# Knobber_Topsheet.net
KiCad netlist of a schematic drawn in Altium Designer
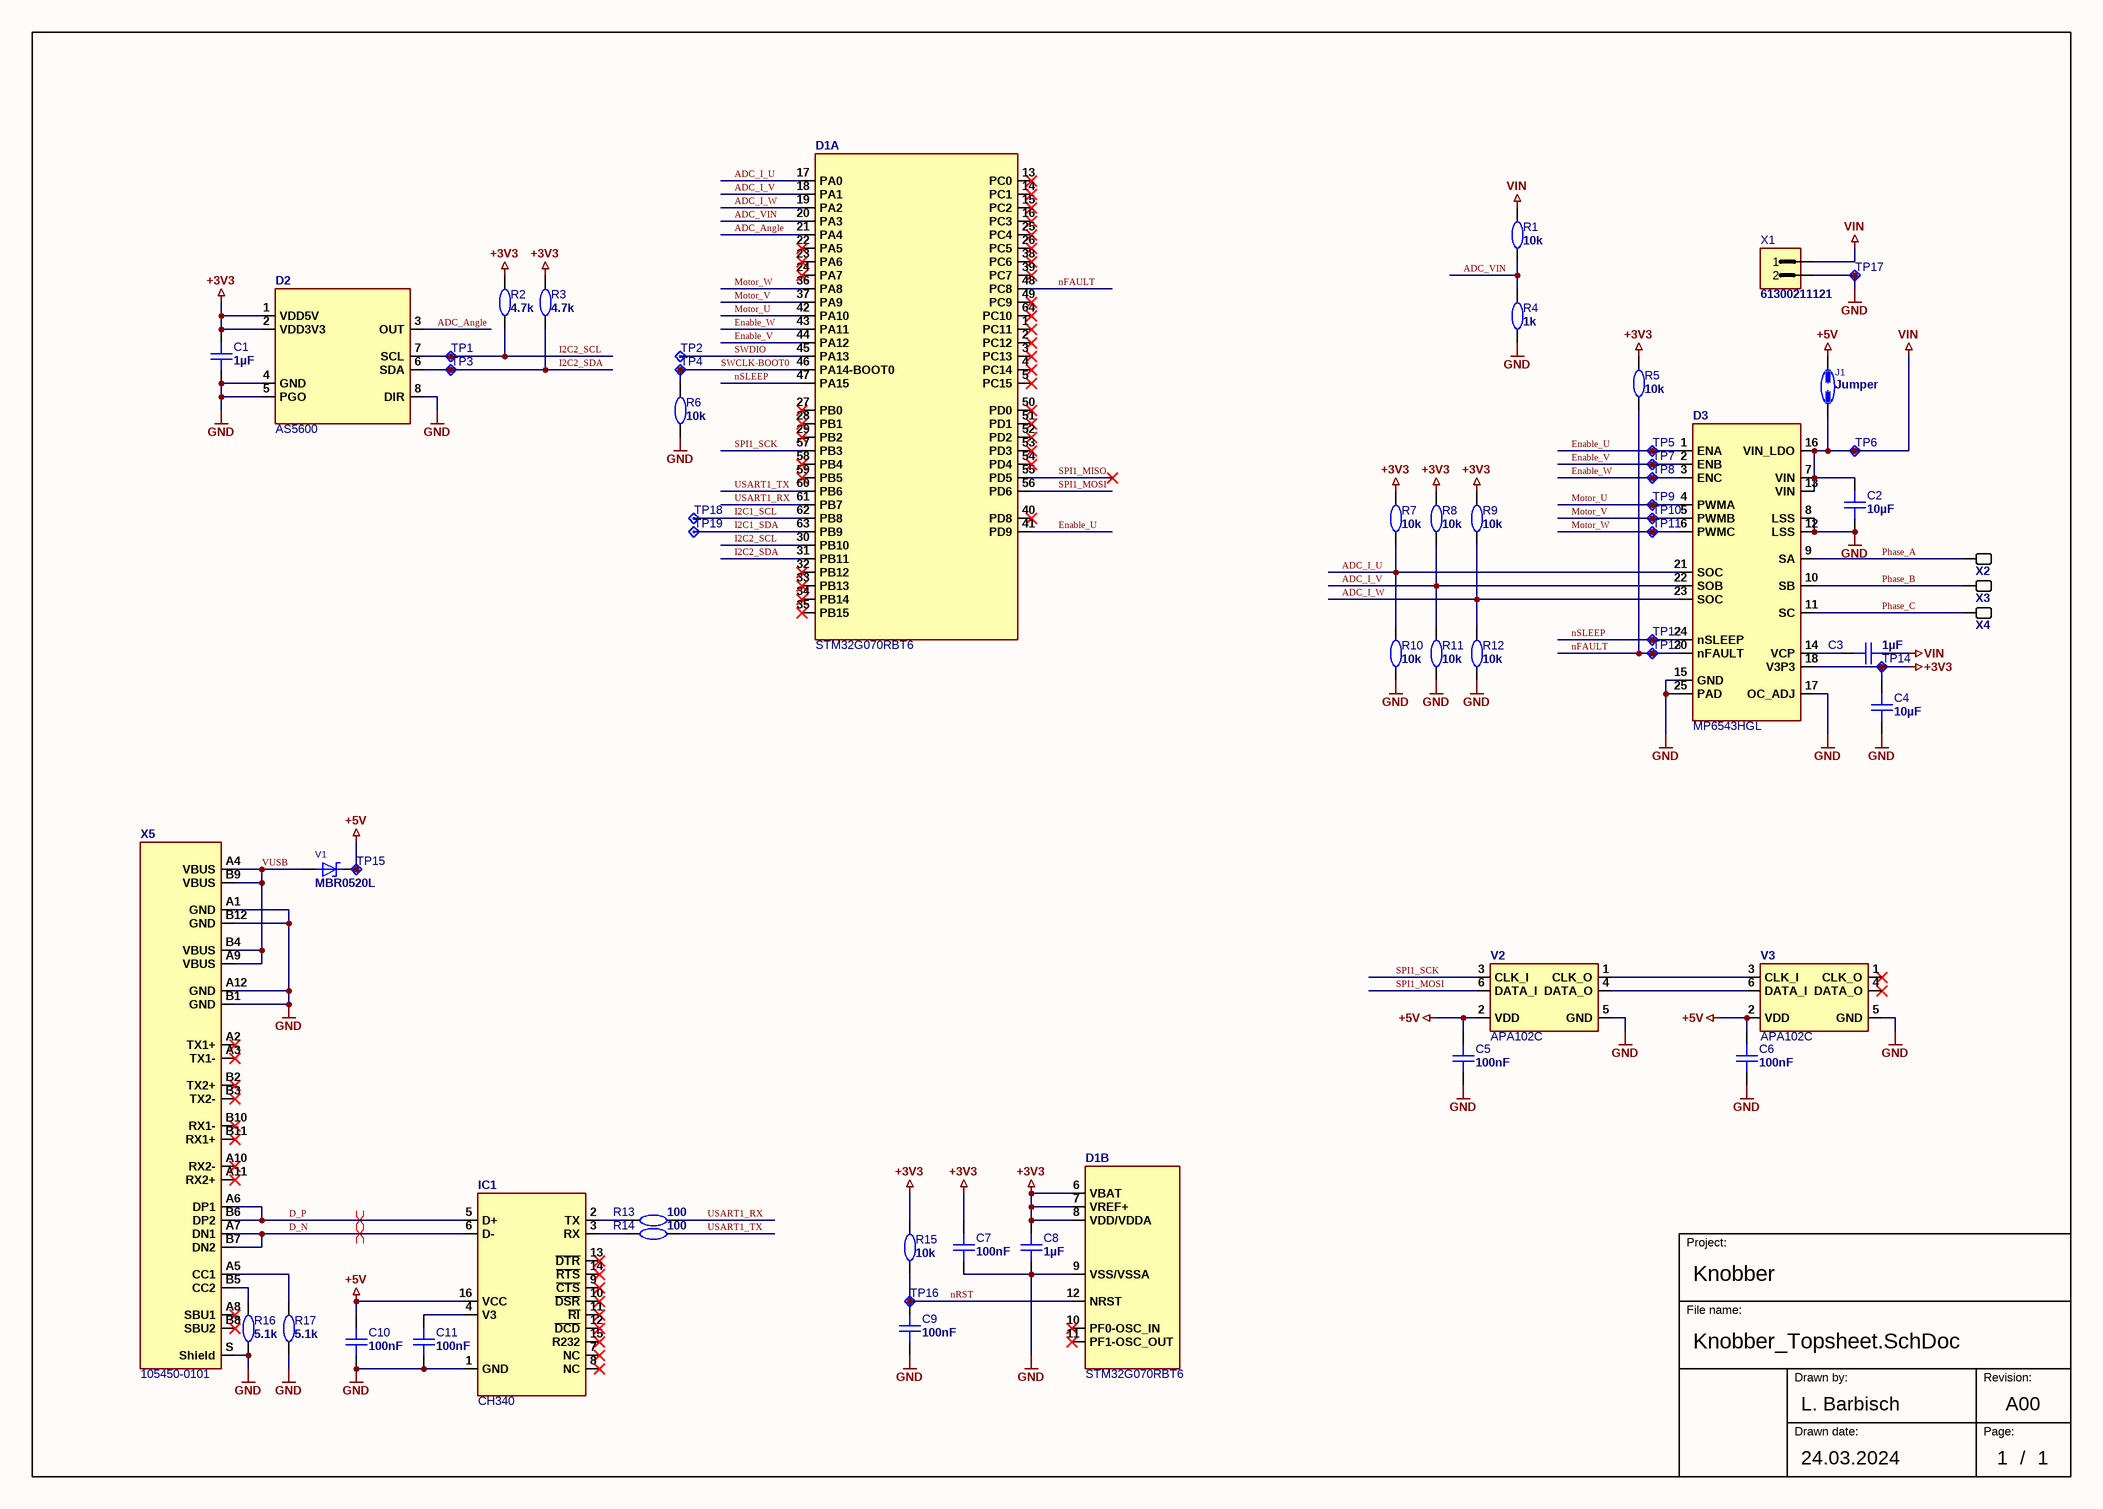
[diagram p0: Knobber_Topsheet.SchDoc]

(export (version "E")
  (design (tool "Eeschema 10.0.6"))
  (components
    (comp (ref "C1")
      (value "1µF")
      (footprint "C-0603_1608_095_L_RF")
      (description "Cap Cer SMD 1u 16V 10% 0603 X7R")
      (fields
        (field (name "MANUFACTURER PART NUMBER") "0603YC105KAT2A")
        (field (name "MANUFACTURER") "AVX")
        (field (name "USER") "epph")
      )
      (libsource (lib "GPV Switzerland SA") (part "CAP"))
    )
    (comp (ref "C2")
      (value "10µF")
      (footprint "C-1210_3225_230_L_RF")
      (description "CAP CER 10uF 50V X7S 1210")
      (fields
        (field (name "MANUFACTURER") "TDK")
        (field (name "MANUFACTURER PART NUMBER") "C3225X7S1H106K250AE")
        (field (name "USER") "zupa")
      )
      (libsource (lib "GPV Switzerland SA") (part "CAP"))
    )
    (comp (ref "C3")
      (value "1µF")
      (footprint "C-0603_1608_095_L_RF")
      (description "Cap Cer SMD 1u 16V 10% 0603 X7R")
      (fields
        (field (name "MANUFACTURER PART NUMBER") "0603YC105KAT2A")
        (field (name "MANUFACTURER") "AVX")
        (field (name "USER") "epph")
      )
      (libsource (lib "GPV Switzerland SA") (part "CAP"))
    )
    (comp (ref "C4")
      (value "10µF")
      (footprint "C-0805_2012_145_L_RF")
      (description "Cap Cer SMD 10u 16V 10% 0805 X5R")
      (fields
        (field (name "MANUFACTURER PART NUMBER") "0805YD106KAT2A")
        (field (name "MANUFACTURER") "AVX")
        (field (name "USER") "zupa")
      )
      (libsource (lib "GPV Switzerland SA") (part "CAP"))
    )
    (comp (ref "C5")
      (value "100nF")
      (footprint "C-0603_1608_095_L_RF")
      (description "Cap Cer SMD 100n 100V 10% 0603 X7R")
      (fields
        (field (name "MANUFACTURER PART NUMBER") "GRM188R72A104KA35")
        (field (name "MANUFACTURER") "MURATA")
        (field (name "USER") "zupa")
      )
      (libsource (lib "GPV Switzerland SA") (part "CAP"))
    )
    (comp (ref "C6")
      (value "100nF")
      (footprint "C-0603_1608_095_L_RF")
      (description "Cap Cer SMD 100n 100V 10% 0603 X7R")
      (fields
        (field (name "MANUFACTURER PART NUMBER") "GRM188R72A104KA35")
        (field (name "MANUFACTURER") "MURATA")
        (field (name "USER") "zupa")
      )
      (libsource (lib "GPV Switzerland SA") (part "CAP"))
    )
    (comp (ref "C7")
      (value "100nF")
      (footprint "C-0603_1608_095_L_RF")
      (description "Cap Cer SMD 100n 100V 10% 0603 X7R")
      (fields
        (field (name "MANUFACTURER PART NUMBER") "GRM188R72A104KA35")
        (field (name "MANUFACTURER") "MURATA")
        (field (name "USER") "zupa")
      )
      (libsource (lib "GPV Switzerland SA") (part "CAP"))
    )
    (comp (ref "C8")
      (value "1µF")
      (footprint "C-0603_1608_095_L_RF")
      (description "Cap Cer SMD 1u 16V 10% 0603 X7R")
      (fields
        (field (name "MANUFACTURER PART NUMBER") "0603YC105KAT2A")
        (field (name "MANUFACTURER") "AVX")
        (field (name "USER") "epph")
      )
      (libsource (lib "GPV Switzerland SA") (part "CAP"))
    )
    (comp (ref "C9")
      (value "100nF")
      (footprint "C-0603_1608_095_L_RF")
      (description "Cap Cer SMD 100n 100V 10% 0603 X7R")
      (fields
        (field (name "MANUFACTURER PART NUMBER") "GRM188R72A104KA35")
        (field (name "MANUFACTURER") "MURATA")
        (field (name "USER") "zupa")
      )
      (libsource (lib "GPV Switzerland SA") (part "CAP"))
    )
    (comp (ref "C10")
      (value "100nF")
      (footprint "C-0603_1608_095_L_RF")
      (description "Cap Cer SMD 100n 100V 10% 0603 X7R")
      (fields
        (field (name "MANUFACTURER PART NUMBER") "GRM188R72A104KA35")
        (field (name "MANUFACTURER") "MURATA")
        (field (name "USER") "zupa")
      )
      (libsource (lib "GPV Switzerland SA") (part "CAP"))
    )
    (comp (ref "C11")
      (value "100nF")
      (footprint "C-0603_1608_095_L_RF")
      (description "Cap Cer SMD 100n 100V 10% 0603 X7R")
      (fields
        (field (name "MANUFACTURER PART NUMBER") "GRM188R72A104KA35")
        (field (name "MANUFACTURER") "MURATA")
        (field (name "USER") "zupa")
      )
      (libsource (lib "GPV Switzerland SA") (part "CAP"))
    )
    (comp (ref "D1")
      (value "STM32G070RBT6")
      (footprint "LQFP64_50P1200X1200X160-64N")
      (description "IC MCU Cortex M0+ 128k Flash, 36k RAM, 64MHz")
      (fields (field (name "MANUFACTURER") "ST"))
      (libsource (lib "Global Library") (part "STM32G070RBT6"))
    )
    (comp (ref "D2")
      (value "AS5600")
      (footprint "SOIC8_N_RF")
      (description "IC Sensor Rotation Magnet 12bit")
      (fields (field (name "MANUFACTURER") "AMS"))
      (libsource (lib "Global Library") (part "AS5600"))
    )
    (comp (ref "D3")
      (value "MP6543HGL")
      (footprint "QFN24_5x7_N_RF")
      (description "Motor Driver 3-Phase 3-22V 2A")
      (fields
        (field (name "MANUFACTURER") "Monolithic Power Systems")
        (field (name "MANUFACTURER PART NUMBER") "MP6543HGL-A-P")
      )
      (libsource (lib "Global Library") (part "MP6543HGL-A-P"))
    )
    (comp (ref "IC1")
      (value "CH340")
      (footprint "SOIC16_N_RF")
      (description "IC Converter USB UART")
      (fields (field (name "MANUFACTURER") "WCN") (field (name "MANUFACTURER PART NUMBER") "CH340C"))
      (libsource (lib "Global Library") (part "CH340C"))
    )
    (comp (ref "J1")
      (value "Jumper")
      (footprint "J-1206_Solderjumper_2Pin")
      (description "Solder jumper 2Pin")
      (fields (field (name "USER") "epph"))
      (libsource (lib "GPV Switzerland SA") (part "Solder jumper 2Pin"))
    )
    (comp (ref "R1")
      (value "10k")
      (footprint "R-0603_1608_050_L_RF")
      (description "Res SMD 10k 1% 0.1W 0603")
      (fields
        (field (name "MANUFACTURER") "YAGEO")
        (field (name "MANUFACTURER PART NUMBER") "RC0603FR-0710KL")
        (field (name "USER") "zupa")
      )
      (libsource (lib "GPV Switzerland SA") (part "RES"))
    )
    (comp (ref "R2")
      (value "4.7k")
      (footprint "R-0603_1608_050_L_RF")
      (description "Res SMD 4k7 1% 0.1W 0603")
      (fields
        (field (name "MANUFACTURER PART NUMBER") "RC0603FR-074K7L")
        (field (name "MANUFACTURER") "YAGEO")
        (field (name "USER") "zupa")
      )
      (libsource (lib "GPV Switzerland SA") (part "RES"))
    )
    (comp (ref "R3")
      (value "4.7k")
      (footprint "R-0603_1608_050_L_RF")
      (description "Res SMD 4k7 1% 0.1W 0603")
      (fields
        (field (name "MANUFACTURER PART NUMBER") "RC0603FR-074K7L")
        (field (name "MANUFACTURER") "YAGEO")
        (field (name "USER") "zupa")
      )
      (libsource (lib "GPV Switzerland SA") (part "RES"))
    )
    (comp (ref "R4")
      (value "1k")
      (footprint "R-0603_1608_050_L_RF")
      (description "Res SMD 1k 1% 0.1W 0603")
      (fields
        (field (name "MANUFACTURER") "YAGEO")
        (field (name "MANUFACTURER PART NUMBER") "RC0603FR-071KL")
        (field (name "USER") "zupa")
      )
      (libsource (lib "GPV Switzerland SA") (part "RES"))
    )
    (comp (ref "R5")
      (value "10k")
      (footprint "R-0603_1608_050_L_RF")
      (description "Res SMD 10k 1% 0.1W 0603")
      (fields
        (field (name "MANUFACTURER") "YAGEO")
        (field (name "MANUFACTURER PART NUMBER") "RC0603FR-0710KL")
        (field (name "USER") "zupa")
      )
      (libsource (lib "GPV Switzerland SA") (part "RES"))
    )
    (comp (ref "R6")
      (value "10k")
      (footprint "R-0603_1608_050_L_RF")
      (description "Res SMD 10k 1% 0.1W 0603")
      (fields
        (field (name "MANUFACTURER") "YAGEO")
        (field (name "MANUFACTURER PART NUMBER") "RC0603FR-0710KL")
        (field (name "USER") "zupa")
      )
      (libsource (lib "GPV Switzerland SA") (part "RES"))
    )
    (comp (ref "R7")
      (value "10k")
      (footprint "R-0603_1608_050_L_RF")
      (description "Res SMD 10k 1% 0.1W 0603")
      (fields
        (field (name "MANUFACTURER") "YAGEO")
        (field (name "MANUFACTURER PART NUMBER") "RC0603FR-0710KL")
        (field (name "USER") "zupa")
      )
      (libsource (lib "GPV Switzerland SA") (part "RES"))
    )
    (comp (ref "R8")
      (value "10k")
      (footprint "R-0603_1608_050_L_RF")
      (description "Res SMD 10k 1% 0.1W 0603")
      (fields
        (field (name "MANUFACTURER") "YAGEO")
        (field (name "MANUFACTURER PART NUMBER") "RC0603FR-0710KL")
        (field (name "USER") "zupa")
      )
      (libsource (lib "GPV Switzerland SA") (part "RES"))
    )
    (comp (ref "R9")
      (value "10k")
      (footprint "R-0603_1608_050_L_RF")
      (description "Res SMD 10k 1% 0.1W 0603")
      (fields
        (field (name "MANUFACTURER") "YAGEO")
        (field (name "MANUFACTURER PART NUMBER") "RC0603FR-0710KL")
        (field (name "USER") "zupa")
      )
      (libsource (lib "GPV Switzerland SA") (part "RES"))
    )
    (comp (ref "R10")
      (value "10k")
      (footprint "R-0603_1608_050_L_RF")
      (description "Res SMD 10k 1% 0.1W 0603")
      (fields
        (field (name "MANUFACTURER") "YAGEO")
        (field (name "MANUFACTURER PART NUMBER") "RC0603FR-0710KL")
        (field (name "USER") "zupa")
      )
      (libsource (lib "GPV Switzerland SA") (part "RES"))
    )
    (comp (ref "R11")
      (value "10k")
      (footprint "R-0603_1608_050_L_RF")
      (description "Res SMD 10k 1% 0.1W 0603")
      (fields
        (field (name "MANUFACTURER") "YAGEO")
        (field (name "MANUFACTURER PART NUMBER") "RC0603FR-0710KL")
        (field (name "USER") "zupa")
      )
      (libsource (lib "GPV Switzerland SA") (part "RES"))
    )
    (comp (ref "R12")
      (value "10k")
      (footprint "R-0603_1608_050_L_RF")
      (description "Res SMD 10k 1% 0.1W 0603")
      (fields
        (field (name "MANUFACTURER") "YAGEO")
        (field (name "MANUFACTURER PART NUMBER") "RC0603FR-0710KL")
        (field (name "USER") "zupa")
      )
      (libsource (lib "GPV Switzerland SA") (part "RES"))
    )
    (comp (ref "R13")
      (value "100")
      (footprint "R-0603_1608_050_L_RF")
      (description "Res SMD 100R 1% 0.1W 0603")
      (fields
        (field (name "MANUFACTURER") "YAGEO")
        (field (name "MANUFACTURER PART NUMBER") "RC0603FR-07100RL")
        (field (name "USER") "zupa")
      )
      (libsource (lib "GPV Switzerland SA") (part "RES"))
    )
    (comp (ref "R14")
      (value "100")
      (footprint "R-0603_1608_050_L_RF")
      (description "Res SMD 100R 1% 0.1W 0603")
      (fields
        (field (name "MANUFACTURER") "YAGEO")
        (field (name "MANUFACTURER PART NUMBER") "RC0603FR-07100RL")
        (field (name "USER") "zupa")
      )
      (libsource (lib "GPV Switzerland SA") (part "RES"))
    )
    (comp (ref "R15")
      (value "10k")
      (footprint "R-0603_1608_050_L_RF")
      (description "Res SMD 10k 1% 0.1W 0603")
      (fields
        (field (name "MANUFACTURER") "YAGEO")
        (field (name "MANUFACTURER PART NUMBER") "RC0603FR-0710KL")
        (field (name "USER") "zupa")
      )
      (libsource (lib "GPV Switzerland SA") (part "RES"))
    )
    (comp (ref "R16")
      (value "5.1k")
      (footprint "R-0603_1608_050_L_RF")
      (description "Res SMD 5k1 1% 0.1W 0603")
      (fields
        (field (name "MANUFACTURER PART NUMBER") "RC0603FR-075K1L")
        (field (name "MANUFACTURER") "YAGEO")
        (field (name "USER") "napa")
      )
      (libsource (lib "GPV Switzerland SA") (part "RES"))
    )
    (comp (ref "R17")
      (value "5.1k")
      (footprint "R-0603_1608_050_L_RF")
      (description "Res SMD 5k1 1% 0.1W 0603")
      (fields
        (field (name "MANUFACTURER PART NUMBER") "RC0603FR-075K1L")
        (field (name "MANUFACTURER") "YAGEO")
        (field (name "USER") "napa")
      )
      (libsource (lib "GPV Switzerland SA") (part "RES"))
    )
    (comp (ref "TP1")
      (value "TestPoint 0.8mm")
      (footprint "TP_0.8mm")
      (fields (field (name "USER") "zupa"))
      (libsource (lib "GPV Switzerland SA") (part "Testpoint"))
    )
    (comp (ref "TP2")
      (value "TestPoint 0.8mm")
      (footprint "TP_0.8mm")
      (fields (field (name "USER") "zupa"))
      (libsource (lib "GPV Switzerland SA") (part "Testpoint"))
    )
    (comp (ref "TP3")
      (value "TestPoint 0.8mm")
      (footprint "TP_0.8mm")
      (fields (field (name "USER") "zupa"))
      (libsource (lib "GPV Switzerland SA") (part "Testpoint"))
    )
    (comp (ref "TP4")
      (value "TestPoint 0.8mm")
      (footprint "TP_0.8mm")
      (fields (field (name "USER") "zupa"))
      (libsource (lib "GPV Switzerland SA") (part "Testpoint"))
    )
    (comp (ref "TP5")
      (value "TestPoint 0.8mm")
      (footprint "TP_0.8mm")
      (fields (field (name "USER") "zupa"))
      (libsource (lib "GPV Switzerland SA") (part "Testpoint"))
    )
    (comp (ref "TP6")
      (value "TestPoint 0.8mm")
      (footprint "TP_0.8mm")
      (fields (field (name "USER") "zupa"))
      (libsource (lib "GPV Switzerland SA") (part "Testpoint"))
    )
    (comp (ref "TP7")
      (value "TestPoint 0.8mm")
      (footprint "TP_0.8mm")
      (fields (field (name "USER") "zupa"))
      (libsource (lib "GPV Switzerland SA") (part "Testpoint"))
    )
    (comp (ref "TP8")
      (value "TestPoint 0.8mm")
      (footprint "TP_0.8mm")
      (fields (field (name "USER") "zupa"))
      (libsource (lib "GPV Switzerland SA") (part "Testpoint"))
    )
    (comp (ref "TP9")
      (value "TestPoint 0.8mm")
      (footprint "TP_0.8mm")
      (fields (field (name "USER") "zupa"))
      (libsource (lib "GPV Switzerland SA") (part "Testpoint"))
    )
    (comp (ref "TP10")
      (value "TestPoint 0.8mm")
      (footprint "TP_0.8mm")
      (fields (field (name "USER") "zupa"))
      (libsource (lib "GPV Switzerland SA") (part "Testpoint"))
    )
    (comp (ref "TP11")
      (value "TestPoint 0.8mm")
      (footprint "TP_0.8mm")
      (fields (field (name "USER") "zupa"))
      (libsource (lib "GPV Switzerland SA") (part "Testpoint"))
    )
    (comp (ref "TP12")
      (value "TestPoint 0.8mm")
      (footprint "TP_0.8mm")
      (fields (field (name "USER") "zupa"))
      (libsource (lib "GPV Switzerland SA") (part "Testpoint"))
    )
    (comp (ref "TP13")
      (value "TestPoint 0.8mm")
      (footprint "TP_0.8mm")
      (fields (field (name "USER") "zupa"))
      (libsource (lib "GPV Switzerland SA") (part "Testpoint"))
    )
    (comp (ref "TP14")
      (value "TestPoint 0.8mm")
      (footprint "TP_0.8mm")
      (fields (field (name "USER") "zupa"))
      (libsource (lib "GPV Switzerland SA") (part "Testpoint"))
    )
    (comp (ref "TP15")
      (value "TestPoint 0.8mm")
      (footprint "TP_0.8mm")
      (fields (field (name "USER") "zupa"))
      (libsource (lib "GPV Switzerland SA") (part "Testpoint"))
    )
    (comp (ref "TP16")
      (value "TestPoint 0.8mm")
      (footprint "TP_0.8mm")
      (fields (field (name "USER") "zupa"))
      (libsource (lib "GPV Switzerland SA") (part "Testpoint"))
    )
    (comp (ref "TP17")
      (value "TestPoint 0.8mm")
      (footprint "TP_0.8mm")
      (fields (field (name "USER") "zupa"))
      (libsource (lib "GPV Switzerland SA") (part "Testpoint"))
    )
    (comp (ref "TP18")
      (value "TestPoint 0.8mm")
      (footprint "TP_0.8mm")
      (fields (field (name "USER") "zupa"))
      (libsource (lib "GPV Switzerland SA") (part "Testpoint"))
    )
    (comp (ref "TP19")
      (value "TestPoint 0.8mm")
      (footprint "TP_0.8mm")
      (fields (field (name "USER") "zupa"))
      (libsource (lib "GPV Switzerland SA") (part "Testpoint"))
    )
    (comp (ref "V1")
      (value "MBR0520L")
      (footprint "SOD123_L_RF")
      (description "Diode Schottky 20V 0.5A SOD123")
      (fields
        (field (name "MANUFACTURER") "ONSemi")
        (field (name "MANUFACTURER PART NUMBER") "MBR0520LT1G")
        (field (name "USER") "epph")
      )
      (libsource (lib "GPV Switzerland SA") (part "SCHOTTKY"))
    )
    (comp (ref "V2")
      (value "APA102C")
      (footprint "V_2020_P6_N_RF")
      (description "RGB LED SPI Interface")
      (fields
        (field (name "MANUFACTURER") "APA Electronic CO")
        (field (name "MANUFACTURER PART NUMBER") "APA-102-2020-256-8A")
      )
      (libsource (lib "Global Library") (part "APA102C"))
    )
    (comp (ref "V3")
      (value "APA102C")
      (footprint "V_2020_P6_N_RF")
      (description "RGB LED SPI Interface")
      (fields
        (field (name "MANUFACTURER") "APA Electronic CO")
        (field (name "MANUFACTURER PART NUMBER") "APA-102-2020-256-8A")
      )
      (libsource (lib "Global Library") (part "APA102C"))
    )
    (comp (ref "X1")
      (value "61300211121")
      (footprint "X-0508X0254_R_WE_61300211121")
      (description "CONN HEADER 2POS 1ROW THT 2.54MM WE 61300211121")
      (fields
        (field (name "MANUFACTURER") "WE")
        (field (name "Comment") "CONN HEADER 2POS 1ROW THT 2.54MM")
        (field (name "USER") "balu")
      )
      (libsource (lib "GPV Switzerland SA") (part "Connector-2P"))
    )
    (comp (ref "X2")
      (value "~")
      (footprint "Lötpad_2x3")
      (description "Solderpad 2mm x 3mm")
      (libsource (lib "Global Library") (part "Lötpad_2mmx3mm"))
    )
    (comp (ref "X3")
      (value "~")
      (footprint "Lötpad_2x3")
      (description "Solderpad 2mm x 3mm")
      (libsource (lib "Global Library") (part "Lötpad_2mmx3mm"))
    )
    (comp (ref "X4")
      (value "~")
      (footprint "Lötpad_2x3")
      (description "Solderpad 2mm x 3mm")
      (libsource (lib "Global Library") (part "Lötpad_2mmx3mm"))
    )
    (comp (ref "X5")
      (value "105450-0101")
      (footprint "105450-0101")
      (description "CONN USB-C 16pin")
      (fields (field (name "MANUFACTURER") "Molex"))
      (libsource (lib "Global Library") (part "105450-0101"))
    )
  )
  (nets
    (net (code "1") (name "+3V3") (class "Default")
      (node (ref "C1") (pin "2") (pinfunction "2_2") (pintype "passive"))
      (node (ref "C4") (pin "2") (pinfunction "2_2") (pintype "passive"))
      (node (ref "C7") (pin "2") (pinfunction "2_2") (pintype "passive"))
      (node (ref "C8") (pin "2") (pinfunction "2_2") (pintype "passive"))
      (node (ref "D1") (pin "6") (pinfunction "VBAT_6") (pintype "passive"))
      (node (ref "D1") (pin "7") (pinfunction "VREF+_7") (pintype "passive"))
      (node (ref "D1") (pin "8") (pinfunction "VDD/VDDA_8") (pintype "passive"))
      (node (ref "D2") (pin "1") (pinfunction "VDD5V_1") (pintype "passive"))
      (node (ref "D2") (pin "2") (pinfunction "VDD3V3_2") (pintype "passive"))
      (node (ref "D3") (pin "18") (pinfunction "V3P3_18") (pintype "passive"))
      (node (ref "R15") (pin "1") (pinfunction "1_1") (pintype "passive"))
      (node (ref "R2") (pin "2") (pinfunction "2_2") (pintype "passive"))
      (node (ref "R3") (pin "2") (pinfunction "2_2") (pintype "passive"))
      (node (ref "R5") (pin "2") (pinfunction "2_2") (pintype "passive"))
      (node (ref "R7") (pin "2") (pinfunction "2_2") (pintype "passive"))
      (node (ref "R8") (pin "2") (pinfunction "2_2") (pintype "passive"))
      (node (ref "R9") (pin "2") (pinfunction "2_2") (pintype "passive"))
      (node (ref "TP14") (pin "1") (pinfunction "1_1") (pintype "passive"))
    )
    (net (code "2") (name "+5V") (class "Default")
      (node (ref "C10") (pin "2") (pinfunction "2_2") (pintype "passive"))
      (node (ref "C5") (pin "2") (pinfunction "2_2") (pintype "passive"))
      (node (ref "C6") (pin "2") (pinfunction "2_2") (pintype "passive"))
      (node (ref "IC1") (pin "16") (pinfunction "VCC_16") (pintype "passive"))
      (node (ref "J1") (pin "2") (pinfunction "2_2") (pintype "passive"))
      (node (ref "TP15") (pin "1") (pinfunction "1_1") (pintype "passive"))
      (node (ref "V1") (pin "2") (pinfunction "2_2") (pintype "passive"))
      (node (ref "V2") (pin "2") (pinfunction "VDD_2") (pintype "passive"))
      (node (ref "V3") (pin "2") (pinfunction "VDD_2") (pintype "passive"))
    )
    (net (code "3") (name "/ADC_Angle") (class "Default")
      (node (ref "D1") (pin "21") (pinfunction "PA4_21") (pintype "passive"))
      (node (ref "D2") (pin "3") (pinfunction "OUT_3") (pintype "passive"))
    )
    (net (code "4") (name "/ADC_I_U") (class "Default")
      (node (ref "D1") (pin "17") (pinfunction "PA0_17") (pintype "passive"))
      (node (ref "D3") (pin "21") (pinfunction "SOC_21") (pintype "passive"))
      (node (ref "R10") (pin "2") (pinfunction "2_2") (pintype "passive"))
      (node (ref "R7") (pin "1") (pinfunction "1_1") (pintype "passive"))
    )
    (net (code "5") (name "/ADC_I_V") (class "Default")
      (node (ref "D1") (pin "18") (pinfunction "PA1_18") (pintype "passive"))
      (node (ref "D3") (pin "22") (pinfunction "SOB_22") (pintype "passive"))
      (node (ref "R11") (pin "2") (pinfunction "2_2") (pintype "passive"))
      (node (ref "R8") (pin "1") (pinfunction "1_1") (pintype "passive"))
    )
    (net (code "6") (name "/ADC_I_W") (class "Default")
      (node (ref "D1") (pin "19") (pinfunction "PA2_19") (pintype "passive"))
      (node (ref "D3") (pin "23") (pinfunction "SOC_23") (pintype "passive"))
      (node (ref "R12") (pin "2") (pinfunction "2_2") (pintype "passive"))
      (node (ref "R9") (pin "1") (pinfunction "1_1") (pintype "passive"))
    )
    (net (code "7") (name "/ADC_VIN") (class "Default")
      (node (ref "D1") (pin "20") (pinfunction "PA3_20") (pintype "passive"))
      (node (ref "R1") (pin "1") (pinfunction "1_1") (pintype "passive"))
      (node (ref "R4") (pin "2") (pinfunction "2_2") (pintype "passive"))
    )
    (net (code "8") (name "/D_N") (class "Default")
      (node (ref "IC1") (pin "6") (pinfunction "D-_6") (pintype "passive"))
      (node (ref "X5") (pin "A7") (pinfunction "DN1_A7") (pintype "passive"))
      (node (ref "X5") (pin "B7") (pinfunction "DN2_B7") (pintype "passive"))
    )
    (net (code "9") (name "/D_P") (class "Default")
      (node (ref "IC1") (pin "5") (pinfunction "D+_5") (pintype "passive"))
      (node (ref "X5") (pin "A6") (pinfunction "DP1_A6") (pintype "passive"))
      (node (ref "X5") (pin "B6") (pinfunction "DP2_B6") (pintype "passive"))
    )
    (net (code "10") (name "/Enable_U") (class "Default")
      (node (ref "D1") (pin "41") (pinfunction "PD9_41") (pintype "passive"))
      (node (ref "D3") (pin "1") (pinfunction "ENA_1") (pintype "passive"))
      (node (ref "TP5") (pin "1") (pinfunction "1_1") (pintype "passive"))
    )
    (net (code "11") (name "/Enable_V") (class "Default")
      (node (ref "D1") (pin "44") (pinfunction "PA12_44") (pintype "passive"))
      (node (ref "D3") (pin "2") (pinfunction "ENB_2") (pintype "passive"))
      (node (ref "TP7") (pin "1") (pinfunction "1_1") (pintype "passive"))
    )
    (net (code "12") (name "/Enable_W") (class "Default")
      (node (ref "D1") (pin "43") (pinfunction "PA11_43") (pintype "passive"))
      (node (ref "D3") (pin "3") (pinfunction "ENC_3") (pintype "passive"))
      (node (ref "TP8") (pin "1") (pinfunction "1_1") (pintype "passive"))
    )
    (net (code "13") (name "/I2C1_SCL") (class "Default")
      (node (ref "D1") (pin "62") (pinfunction "PB8_62") (pintype "passive"))
      (node (ref "TP18") (pin "1") (pinfunction "1_1") (pintype "passive"))
    )
    (net (code "14") (name "/I2C1_SDA") (class "Default")
      (node (ref "D1") (pin "63") (pinfunction "PB9_63") (pintype "passive"))
      (node (ref "TP19") (pin "1") (pinfunction "1_1") (pintype "passive"))
    )
    (net (code "15") (name "/I2C2_SCL") (class "Default")
      (node (ref "D1") (pin "30") (pinfunction "PB10_30") (pintype "passive"))
      (node (ref "D2") (pin "7") (pinfunction "SCL_7") (pintype "passive"))
      (node (ref "R2") (pin "1") (pinfunction "1_1") (pintype "passive"))
      (node (ref "TP1") (pin "1") (pinfunction "1_1") (pintype "passive"))
    )
    (net (code "16") (name "/I2C2_SDA") (class "Default")
      (node (ref "D1") (pin "31") (pinfunction "PB11_31") (pintype "passive"))
      (node (ref "D2") (pin "6") (pinfunction "SDA_6") (pintype "passive"))
      (node (ref "R3") (pin "1") (pinfunction "1_1") (pintype "passive"))
      (node (ref "TP3") (pin "1") (pinfunction "1_1") (pintype "passive"))
    )
    (net (code "17") (name "/Motor_U") (class "Default")
      (node (ref "D1") (pin "42") (pinfunction "PA10_42") (pintype "passive"))
      (node (ref "D3") (pin "4") (pinfunction "PWMA_4") (pintype "passive"))
      (node (ref "TP9") (pin "1") (pinfunction "1_1") (pintype "passive"))
    )
    (net (code "18") (name "/Motor_V") (class "Default")
      (node (ref "D1") (pin "37") (pinfunction "PA9_37") (pintype "passive"))
      (node (ref "D3") (pin "5") (pinfunction "PWMB_5") (pintype "passive"))
      (node (ref "TP10") (pin "1") (pinfunction "1_1") (pintype "passive"))
    )
    (net (code "19") (name "/Motor_W") (class "Default")
      (node (ref "D1") (pin "36") (pinfunction "PA8_36") (pintype "passive"))
      (node (ref "D3") (pin "6") (pinfunction "PWMC_6") (pintype "passive"))
      (node (ref "TP11") (pin "1") (pinfunction "1_1") (pintype "passive"))
    )
    (net (code "20") (name "/Phase_A") (class "Default")
      (node (ref "D3") (pin "9") (pinfunction "SA_9") (pintype "passive"))
      (node (ref "X2") (pin "1") (pintype "passive"))
    )
    (net (code "21") (name "/Phase_B") (class "Default")
      (node (ref "D3") (pin "10") (pinfunction "SB_10") (pintype "passive"))
      (node (ref "X3") (pin "1") (pintype "passive"))
    )
    (net (code "22") (name "/Phase_C") (class "Default")
      (node (ref "D3") (pin "11") (pinfunction "SC_11") (pintype "passive"))
      (node (ref "X4") (pin "1") (pintype "passive"))
    )
    (net (code "23") (name "/SPI1_MISO") (class "Default")
      (node (ref "D1") (pin "55") (pinfunction "PD5_55") (pintype "passive+no_connect"))
    )
    (net (code "24") (name "/SPI1_MOSI") (class "Default")
      (node (ref "D1") (pin "56") (pinfunction "PD6_56") (pintype "passive"))
      (node (ref "V2") (pin "6") (pinfunction "DATA_I_6") (pintype "passive"))
    )
    (net (code "25") (name "/SPI1_SCK") (class "Default")
      (node (ref "D1") (pin "57") (pinfunction "PB3_57") (pintype "passive"))
      (node (ref "V2") (pin "3") (pinfunction "CLK_I_3") (pintype "passive"))
    )
    (net (code "26") (name "/SWCLK-BOOT0") (class "Default")
      (node (ref "D1") (pin "46") (pinfunction "PA14-BOOT0_46") (pintype "passive"))
      (node (ref "R6") (pin "2") (pinfunction "2_2") (pintype "passive"))
      (node (ref "TP4") (pin "1") (pinfunction "1_1") (pintype "passive"))
    )
    (net (code "27") (name "/SWDIO") (class "Default")
      (node (ref "D1") (pin "45") (pinfunction "PA13_45") (pintype "passive"))
      (node (ref "TP2") (pin "1") (pinfunction "1_1") (pintype "passive"))
    )
    (net (code "28") (name "/USART1_RX") (class "Default")
      (node (ref "D1") (pin "61") (pinfunction "PB7_61") (pintype "passive"))
      (node (ref "R13") (pin "2") (pinfunction "2_2") (pintype "passive"))
    )
    (net (code "29") (name "/USART1_TX") (class "Default")
      (node (ref "D1") (pin "60") (pinfunction "PB6_60") (pintype "passive"))
      (node (ref "R14") (pin "2") (pinfunction "2_2") (pintype "passive"))
    )
    (net (code "30") (name "/VUSB") (class "Default")
      (node (ref "V1") (pin "1") (pinfunction "1_1") (pintype "passive"))
      (node (ref "X5") (pin "A4") (pinfunction "VBUS_A4") (pintype "passive"))
      (node (ref "X5") (pin "A9") (pinfunction "VBUS_A9") (pintype "passive"))
      (node (ref "X5") (pin "B4") (pinfunction "VBUS_B4") (pintype "passive"))
      (node (ref "X5") (pin "B9") (pinfunction "VBUS_B9") (pintype "passive"))
    )
    (net (code "31") (name "/nFAULT") (class "Default")
      (node (ref "D1") (pin "48") (pinfunction "PC8_48") (pintype "passive"))
      (node (ref "D3") (pin "20") (pinfunction "nFAULT_20") (pintype "passive"))
      (node (ref "R5") (pin "1") (pinfunction "1_1") (pintype "passive"))
      (node (ref "TP13") (pin "1") (pinfunction "1_1") (pintype "passive"))
    )
    (net (code "32") (name "/nRST") (class "Default")
      (node (ref "C9") (pin "2") (pinfunction "2_2") (pintype "passive"))
      (node (ref "D1") (pin "12") (pinfunction "NRST_12") (pintype "passive"))
      (node (ref "R15") (pin "2") (pinfunction "2_2") (pintype "passive"))
      (node (ref "TP16") (pin "1") (pinfunction "1_1") (pintype "passive"))
    )
    (net (code "33") (name "/nSLEEP") (class "Default")
      (node (ref "D1") (pin "47") (pinfunction "PA15_47") (pintype "passive"))
      (node (ref "D3") (pin "24") (pinfunction "nSLEEP_24") (pintype "passive"))
      (node (ref "TP12") (pin "1") (pinfunction "1_1") (pintype "passive"))
    )
    (net (code "34") (name "GND") (class "Default")
      (node (ref "C1") (pin "1") (pinfunction "1_1") (pintype "passive"))
      (node (ref "C10") (pin "1") (pinfunction "1_1") (pintype "passive"))
      (node (ref "C11") (pin "1") (pinfunction "1_1") (pintype "passive"))
      (node (ref "C2") (pin "1") (pinfunction "1_1") (pintype "passive"))
      (node (ref "C4") (pin "1") (pinfunction "1_1") (pintype "passive"))
      (node (ref "C5") (pin "1") (pinfunction "1_1") (pintype "passive"))
      (node (ref "C6") (pin "1") (pinfunction "1_1") (pintype "passive"))
      (node (ref "C7") (pin "1") (pinfunction "1_1") (pintype "passive"))
      (node (ref "C8") (pin "1") (pinfunction "1_1") (pintype "passive"))
      (node (ref "C9") (pin "1") (pinfunction "1_1") (pintype "passive"))
      (node (ref "D1") (pin "9") (pinfunction "VSS/VSSA_9") (pintype "passive"))
      (node (ref "D2") (pin "4") (pinfunction "GND_4") (pintype "passive"))
      (node (ref "D2") (pin "5") (pinfunction "PGO_5") (pintype "passive"))
      (node (ref "D2") (pin "8") (pinfunction "DIR_8") (pintype "passive"))
      (node (ref "D3") (pin "12") (pinfunction "LSS_12") (pintype "passive"))
      (node (ref "D3") (pin "15") (pinfunction "GND_15") (pintype "passive"))
      (node (ref "D3") (pin "17") (pinfunction "OC_ADJ_17") (pintype "passive"))
      (node (ref "D3") (pin "25") (pinfunction "PAD_25") (pintype "passive"))
      (node (ref "D3") (pin "8") (pinfunction "LSS_8") (pintype "passive"))
      (node (ref "IC1") (pin "1") (pinfunction "GND_1") (pintype "passive"))
      (node (ref "R10") (pin "1") (pinfunction "1_1") (pintype "passive"))
      (node (ref "R11") (pin "1") (pinfunction "1_1") (pintype "passive"))
      (node (ref "R12") (pin "1") (pinfunction "1_1") (pintype "passive"))
      (node (ref "R16") (pin "1") (pinfunction "1_1") (pintype "passive"))
      (node (ref "R17") (pin "1") (pinfunction "1_1") (pintype "passive"))
      (node (ref "R4") (pin "1") (pinfunction "1_1") (pintype "passive"))
      (node (ref "R6") (pin "1") (pinfunction "1_1") (pintype "passive"))
      (node (ref "TP17") (pin "1") (pinfunction "1_1") (pintype "passive"))
      (node (ref "V2") (pin "5") (pinfunction "GND_5") (pintype "passive"))
      (node (ref "V3") (pin "5") (pinfunction "GND_5") (pintype "passive"))
      (node (ref "X1") (pin "2") (pinfunction "2_2") (pintype "passive"))
      (node (ref "X5") (pin "A1") (pinfunction "GND_A1") (pintype "passive"))
      (node (ref "X5") (pin "A12") (pinfunction "GND_A12") (pintype "passive"))
      (node (ref "X5") (pin "B1") (pinfunction "GND_B1") (pintype "passive"))
      (node (ref "X5") (pin "B12") (pinfunction "GND_B12") (pintype "passive"))
      (node (ref "X5") (pin "S") (pinfunction "Shield_S") (pintype "passive"))
    )
    (net (code "35") (name "Net-(D3-VCP)") (class "Default")
      (node (ref "C3") (pin "1") (pinfunction "1_1") (pintype "passive"))
      (node (ref "D3") (pin "14") (pinfunction "VCP_14") (pintype "passive"))
    )
    (net (code "36") (name "Net-(IC1-RX)") (class "Default")
      (node (ref "IC1") (pin "3") (pinfunction "RX_3") (pintype "passive"))
      (node (ref "R14") (pin "1") (pinfunction "1_1") (pintype "passive"))
    )
    (net (code "37") (name "Net-(IC1-TX)") (class "Default")
      (node (ref "IC1") (pin "2") (pinfunction "TX_2") (pintype "passive"))
      (node (ref "R13") (pin "1") (pinfunction "1_1") (pintype "passive"))
    )
    (net (code "38") (name "Net-(IC1-V3)") (class "Default")
      (node (ref "C11") (pin "2") (pinfunction "2_2") (pintype "passive"))
      (node (ref "IC1") (pin "4") (pinfunction "V3_4") (pintype "passive"))
    )
    (net (code "39") (name "Net-(V2-CLK_O)") (class "Default")
      (node (ref "V2") (pin "1") (pinfunction "CLK_O_1") (pintype "passive"))
      (node (ref "V3") (pin "3") (pinfunction "CLK_I_3") (pintype "passive"))
    )
    (net (code "40") (name "Net-(V2-DATA_O)") (class "Default")
      (node (ref "V2") (pin "4") (pinfunction "DATA_O_4") (pintype "passive"))
      (node (ref "V3") (pin "6") (pinfunction "DATA_I_6") (pintype "passive"))
    )
    (net (code "41") (name "Net-(X5-CC1)") (class "Default")
      (node (ref "R17") (pin "2") (pinfunction "2_2") (pintype "passive"))
      (node (ref "X5") (pin "A5") (pinfunction "CC1_A5") (pintype "passive"))
    )
    (net (code "42") (name "Net-(X5-CC2)") (class "Default")
      (node (ref "R16") (pin "2") (pinfunction "2_2") (pintype "passive"))
      (node (ref "X5") (pin "B5") (pinfunction "CC2_B5") (pintype "passive"))
    )
    (net (code "43") (name "VIN") (class "Default")
      (node (ref "C2") (pin "2") (pinfunction "2_2") (pintype "passive"))
      (node (ref "C3") (pin "2") (pinfunction "2_2") (pintype "passive"))
      (node (ref "D3") (pin "13") (pinfunction "VIN_13") (pintype "passive"))
      (node (ref "D3") (pin "16") (pinfunction "VIN_LDO_16") (pintype "passive"))
      (node (ref "D3") (pin "7") (pinfunction "VIN_7") (pintype "passive"))
      (node (ref "J1") (pin "1") (pinfunction "1_1") (pintype "passive"))
      (node (ref "R1") (pin "2") (pinfunction "2_2") (pintype "passive"))
      (node (ref "TP6") (pin "1") (pinfunction "1_1") (pintype "passive"))
      (node (ref "X1") (pin "1") (pinfunction "1_1") (pintype "passive"))
    )
    (net (code "44") (name "unconnected-(D1A-PA5-Pad22)") (class "Default")
      (node (ref "D1") (pin "22") (pinfunction "PA5_22") (pintype "passive+no_connect"))
    )
    (net (code "45") (name "unconnected-(D1A-PA6-Pad23)") (class "Default")
      (node (ref "D1") (pin "23") (pinfunction "PA6_23") (pintype "passive+no_connect"))
    )
    (net (code "46") (name "unconnected-(D1A-PA7-Pad24)") (class "Default")
      (node (ref "D1") (pin "24") (pinfunction "PA7_24") (pintype "passive+no_connect"))
    )
    (net (code "47") (name "unconnected-(D1A-PB0-Pad27)") (class "Default")
      (node (ref "D1") (pin "27") (pinfunction "PB0_27") (pintype "passive+no_connect"))
    )
    (net (code "48") (name "unconnected-(D1A-PB1-Pad28)") (class "Default")
      (node (ref "D1") (pin "28") (pinfunction "PB1_28") (pintype "passive+no_connect"))
    )
    (net (code "49") (name "unconnected-(D1A-PB2-Pad29)") (class "Default")
      (node (ref "D1") (pin "29") (pinfunction "PB2_29") (pintype "passive+no_connect"))
    )
    (net (code "50") (name "unconnected-(D1A-PB4-Pad58)") (class "Default")
      (node (ref "D1") (pin "58") (pinfunction "PB4_58") (pintype "passive+no_connect"))
    )
    (net (code "51") (name "unconnected-(D1A-PB5-Pad59)") (class "Default")
      (node (ref "D1") (pin "59") (pinfunction "PB5_59") (pintype "passive+no_connect"))
    )
    (net (code "52") (name "unconnected-(D1A-PB12-Pad32)") (class "Default")
      (node (ref "D1") (pin "32") (pinfunction "PB12_32") (pintype "passive+no_connect"))
    )
    (net (code "53") (name "unconnected-(D1A-PB13-Pad33)") (class "Default")
      (node (ref "D1") (pin "33") (pinfunction "PB13_33") (pintype "passive+no_connect"))
    )
    (net (code "54") (name "unconnected-(D1A-PB14-Pad34)") (class "Default")
      (node (ref "D1") (pin "34") (pinfunction "PB14_34") (pintype "passive+no_connect"))
    )
    (net (code "55") (name "unconnected-(D1A-PB15-Pad35)") (class "Default")
      (node (ref "D1") (pin "35") (pinfunction "PB15_35") (pintype "passive+no_connect"))
    )
    (net (code "56") (name "unconnected-(D1A-PC0-Pad13)") (class "Default")
      (node (ref "D1") (pin "13") (pinfunction "PC0_13") (pintype "passive+no_connect"))
    )
    (net (code "57") (name "unconnected-(D1A-PC1-Pad14)") (class "Default")
      (node (ref "D1") (pin "14") (pinfunction "PC1_14") (pintype "passive+no_connect"))
    )
    (net (code "58") (name "unconnected-(D1A-PC2-Pad15)") (class "Default")
      (node (ref "D1") (pin "15") (pinfunction "PC2_15") (pintype "passive+no_connect"))
    )
    (net (code "59") (name "unconnected-(D1A-PC3-Pad16)") (class "Default")
      (node (ref "D1") (pin "16") (pinfunction "PC3_16") (pintype "passive+no_connect"))
    )
    (net (code "60") (name "unconnected-(D1A-PC4-Pad25)") (class "Default")
      (node (ref "D1") (pin "25") (pinfunction "PC4_25") (pintype "passive+no_connect"))
    )
    (net (code "61") (name "unconnected-(D1A-PC5-Pad26)") (class "Default")
      (node (ref "D1") (pin "26") (pinfunction "PC5_26") (pintype "passive+no_connect"))
    )
    (net (code "62") (name "unconnected-(D1A-PC6-Pad38)") (class "Default")
      (node (ref "D1") (pin "38") (pinfunction "PC6_38") (pintype "passive+no_connect"))
    )
    (net (code "63") (name "unconnected-(D1A-PC7-Pad39)") (class "Default")
      (node (ref "D1") (pin "39") (pinfunction "PC7_39") (pintype "passive+no_connect"))
    )
    (net (code "64") (name "unconnected-(D1A-PC9-Pad49)") (class "Default")
      (node (ref "D1") (pin "49") (pinfunction "PC9_49") (pintype "passive+no_connect"))
    )
    (net (code "65") (name "unconnected-(D1A-PC10-Pad64)") (class "Default")
      (node (ref "D1") (pin "64") (pinfunction "PC10_64") (pintype "passive+no_connect"))
    )
    (net (code "66") (name "unconnected-(D1A-PC11-Pad1)") (class "Default")
      (node (ref "D1") (pin "1") (pinfunction "PC11_1") (pintype "passive+no_connect"))
    )
    (net (code "67") (name "unconnected-(D1A-PC12-Pad2)") (class "Default")
      (node (ref "D1") (pin "2") (pinfunction "PC12_2") (pintype "passive+no_connect"))
    )
    (net (code "68") (name "unconnected-(D1A-PC13-Pad3)") (class "Default")
      (node (ref "D1") (pin "3") (pinfunction "PC13_3") (pintype "passive+no_connect"))
    )
    (net (code "69") (name "unconnected-(D1A-PC14-Pad4)") (class "Default")
      (node (ref "D1") (pin "4") (pinfunction "PC14_4") (pintype "passive+no_connect"))
    )
    (net (code "70") (name "unconnected-(D1A-PC15-Pad5)") (class "Default")
      (node (ref "D1") (pin "5") (pinfunction "PC15_5") (pintype "passive+no_connect"))
    )
    (net (code "71") (name "unconnected-(D1A-PD0-Pad50)") (class "Default")
      (node (ref "D1") (pin "50") (pinfunction "PD0_50") (pintype "passive+no_connect"))
    )
    (net (code "72") (name "unconnected-(D1A-PD1-Pad51)") (class "Default")
      (node (ref "D1") (pin "51") (pinfunction "PD1_51") (pintype "passive+no_connect"))
    )
    (net (code "73") (name "unconnected-(D1A-PD2-Pad52)") (class "Default")
      (node (ref "D1") (pin "52") (pinfunction "PD2_52") (pintype "passive+no_connect"))
    )
    (net (code "74") (name "unconnected-(D1A-PD3-Pad53)") (class "Default")
      (node (ref "D1") (pin "53") (pinfunction "PD3_53") (pintype "passive+no_connect"))
    )
    (net (code "75") (name "unconnected-(D1A-PD4-Pad54)") (class "Default")
      (node (ref "D1") (pin "54") (pinfunction "PD4_54") (pintype "passive+no_connect"))
    )
    (net (code "76") (name "unconnected-(D1A-PD8-Pad40)") (class "Default")
      (node (ref "D1") (pin "40") (pinfunction "PD8_40") (pintype "passive+no_connect"))
    )
    (net (code "77") (name "unconnected-(D1B-PF0-OSC_IN-Pad10)") (class "Default")
      (node (ref "D1") (pin "10") (pinfunction "PF0-OSC_IN_10") (pintype "passive+no_connect"))
    )
    (net (code "78") (name "unconnected-(D1B-PF1-OSC_OUT-Pad11)") (class "Default")
      (node (ref "D1") (pin "11") (pinfunction "PF1-OSC_OUT_11") (pintype "passive+no_connect"))
    )
    (net (code "79") (name "unconnected-(IC1-CTS-Pad9)") (class "Default")
      (node (ref "IC1") (pin "9") (pinfunction "CTS_9") (pintype "passive+no_connect"))
    )
    (net (code "80") (name "unconnected-(IC1-DCD-Pad12)") (class "Default")
      (node (ref "IC1") (pin "12") (pinfunction "DCD_12") (pintype "passive+no_connect"))
    )
    (net (code "81") (name "unconnected-(IC1-DSR-Pad10)") (class "Default")
      (node (ref "IC1") (pin "10") (pinfunction "DSR_10") (pintype "passive+no_connect"))
    )
    (net (code "82") (name "unconnected-(IC1-DTR-Pad13)") (class "Default")
      (node (ref "IC1") (pin "13") (pinfunction "DTR_13") (pintype "passive+no_connect"))
    )
    (net (code "83") (name "unconnected-(IC1-NC-Pad7)") (class "Default")
      (node (ref "IC1") (pin "7") (pinfunction "NC_7") (pintype "passive+no_connect"))
    )
    (net (code "84") (name "unconnected-(IC1-NC-Pad8)") (class "Default")
      (node (ref "IC1") (pin "8") (pinfunction "NC_8") (pintype "passive+no_connect"))
    )
    (net (code "85") (name "unconnected-(IC1-R232-Pad15)") (class "Default")
      (node (ref "IC1") (pin "15") (pinfunction "R232_15") (pintype "passive+no_connect"))
    )
    (net (code "86") (name "unconnected-(IC1-RI-Pad11)") (class "Default")
      (node (ref "IC1") (pin "11") (pinfunction "RI_11") (pintype "passive+no_connect"))
    )
    (net (code "87") (name "unconnected-(IC1-RTS-Pad14)") (class "Default")
      (node (ref "IC1") (pin "14") (pinfunction "RTS_14") (pintype "passive+no_connect"))
    )
    (net (code "88") (name "unconnected-(V3-CLK_O-Pad1)") (class "Default")
      (node (ref "V3") (pin "1") (pinfunction "CLK_O_1") (pintype "passive+no_connect"))
    )
    (net (code "89") (name "unconnected-(V3-DATA_O-Pad4)") (class "Default")
      (node (ref "V3") (pin "4") (pinfunction "DATA_O_4") (pintype "passive+no_connect"))
    )
    (net (code "90") (name "unconnected-(X5-RX1+-PadB11)") (class "Default")
      (node (ref "X5") (pin "B11") (pinfunction "RX1+_B11") (pintype "passive+no_connect"))
    )
    (net (code "91") (name "unconnected-(X5-RX1--PadB10)") (class "Default")
      (node (ref "X5") (pin "B10") (pinfunction "RX1-_B10") (pintype "passive+no_connect"))
    )
    (net (code "92") (name "unconnected-(X5-RX2+-PadA11)") (class "Default")
      (node (ref "X5") (pin "A11") (pinfunction "RX2+_A11") (pintype "passive+no_connect"))
    )
    (net (code "93") (name "unconnected-(X5-RX2--PadA10)") (class "Default")
      (node (ref "X5") (pin "A10") (pinfunction "RX2-_A10") (pintype "passive+no_connect"))
    )
    (net (code "94") (name "unconnected-(X5-SBU1-PadA8)") (class "Default")
      (node (ref "X5") (pin "A8") (pinfunction "SBU1_A8") (pintype "passive+no_connect"))
    )
    (net (code "95") (name "unconnected-(X5-SBU2-PadB8)") (class "Default")
      (node (ref "X5") (pin "B8") (pinfunction "SBU2_B8") (pintype "passive+no_connect"))
    )
    (net (code "96") (name "unconnected-(X5-TX1+-PadA2)") (class "Default")
      (node (ref "X5") (pin "A2") (pinfunction "TX1+_A2") (pintype "passive+no_connect"))
    )
    (net (code "97") (name "unconnected-(X5-TX1--PadA3)") (class "Default")
      (node (ref "X5") (pin "A3") (pinfunction "TX1-_A3") (pintype "passive+no_connect"))
    )
    (net (code "98") (name "unconnected-(X5-TX2+-PadB2)") (class "Default")
      (node (ref "X5") (pin "B2") (pinfunction "TX2+_B2") (pintype "passive+no_connect"))
    )
    (net (code "99") (name "unconnected-(X5-TX2--PadB3)") (class "Default")
      (node (ref "X5") (pin "B3") (pinfunction "TX2-_B3") (pintype "passive+no_connect"))
    )
  )
)
